# BANK34_35.net
KiCad netlist of a schematic drawn in Altium Designer
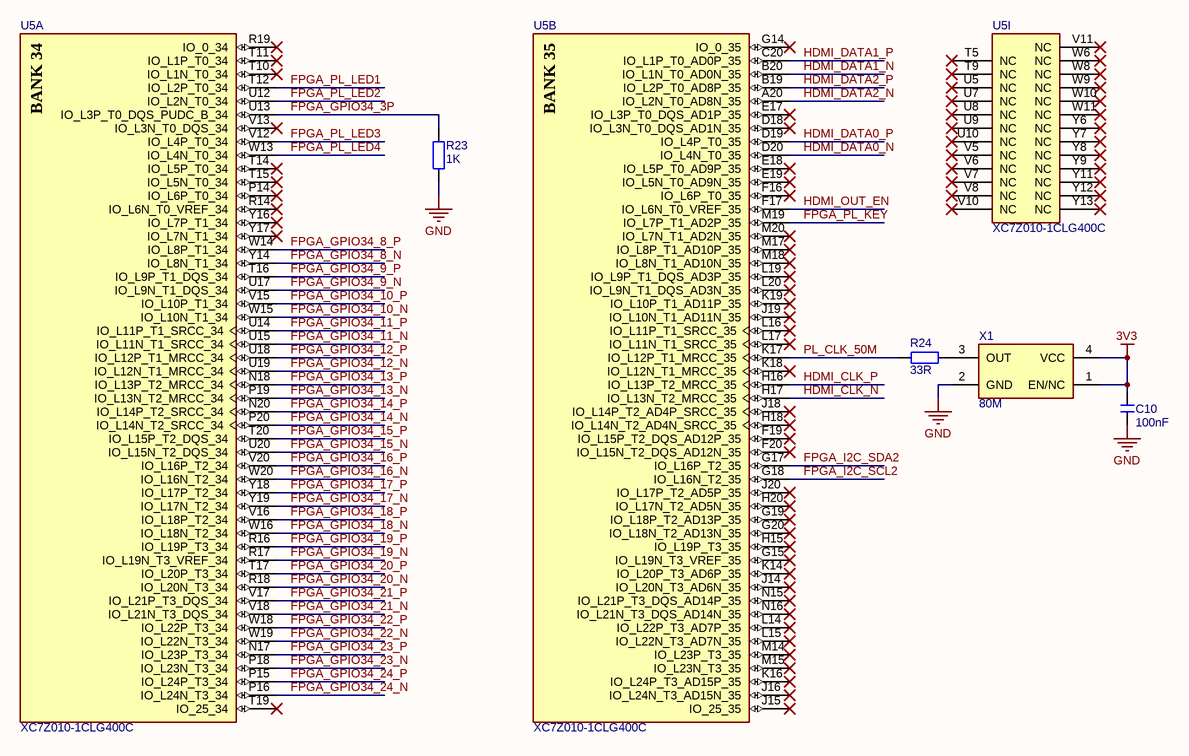
[diagram p0: BANK34_35.SchDoc]

(export (version "E")
  (design (tool "Eeschema 10.0.6"))
  (components
    (comp (ref "C10")
      (value "100nF")
      (footprint "C 0402_L")
      (description "无极性贴片电容")
      (fields (field (name "版权归属") "源创客"))
      (libsource (lib "3.1   - 电阻-电容-电感") (part "C"))
    )
    (comp (ref "R23")
      (value "1K")
      (footprint "R 0402_L")
      (description "贴片电阻")
      (fields (field (name "版权归属") "源创客"))
      (libsource (lib "3.1   - 电阻-电容-电感") (part "R"))
    )
    (comp (ref "R24")
      (value "33R")
      (footprint "R 0805_L")
      (description "贴片电阻")
      (fields (field (name "版权归属") "源创客"))
      (libsource (lib "3.1   - 电阻-电容-电感") (part "R"))
    )
    (comp (ref "U5")
      (value "XC7Z010-1CLG400C")
      (footprint "CLG400")
      (description "ZYNQ7000芯片")
      (libsource (lib "16.2 - Xilinx芯片") (part "XC7Z010-1CLG400C"))
    )
    (comp (ref "X1")
      (value "80M")
      (footprint "OSC 1612-4P")
      (description "4脚有源晶振")
      (fields (field (name "版权归属") "源创客"))
      (libsource (lib "10.1 - 保险丝-晶振") (part "XTAL-ACT-4P"))
    )
  )
  (nets
    (net (code "1") (name "/FPGA_GPIO34_3P") (class "Default")
      (node (ref "R23") (pin "1") (pinfunction "1_1") (pintype "passive"))
      (node (ref "U5") (pin "U13") (pinfunction "IO_L3P_T0_DQS_PUDC_B_34_U13") (pintype "bidirectional"))
    )
    (net (code "2") (name "/FPGA_GPIO34_8_N") (class "Default")
      (node (ref "U5") (pin "Y14") (pinfunction "IO_L8N_T1_34_Y14") (pintype "bidirectional"))
    )
    (net (code "3") (name "/FPGA_GPIO34_8_P") (class "Default")
      (node (ref "U5") (pin "W14") (pinfunction "IO_L8P_T1_34_W14") (pintype "bidirectional"))
    )
    (net (code "4") (name "/FPGA_GPIO34_9_N") (class "Default")
      (node (ref "U5") (pin "U17") (pinfunction "IO_L9N_T1_DQS_34_U17") (pintype "bidirectional"))
    )
    (net (code "5") (name "/FPGA_GPIO34_9_P") (class "Default")
      (node (ref "U5") (pin "T16") (pinfunction "IO_L9P_T1_DQS_34_T16") (pintype "bidirectional"))
    )
    (net (code "6") (name "/FPGA_GPIO34_10_N") (class "Default")
      (node (ref "U5") (pin "W15") (pinfunction "IO_L10N_T1_34_W15") (pintype "bidirectional"))
    )
    (net (code "7") (name "/FPGA_GPIO34_10_P") (class "Default")
      (node (ref "U5") (pin "V15") (pinfunction "IO_L10P_T1_34_V15") (pintype "bidirectional"))
    )
    (net (code "8") (name "/FPGA_GPIO34_11_N") (class "Default")
      (node (ref "U5") (pin "U15") (pinfunction "IO_L11N_T1_SRCC_34_U15") (pintype "bidirectional"))
    )
    (net (code "9") (name "/FPGA_GPIO34_11_P") (class "Default")
      (node (ref "U5") (pin "U14") (pinfunction "IO_L11P_T1_SRCC_34_U14") (pintype "bidirectional"))
    )
    (net (code "10") (name "/FPGA_GPIO34_12_N") (class "Default")
      (node (ref "U5") (pin "U19") (pinfunction "IO_L12N_T1_MRCC_34_U19") (pintype "bidirectional"))
    )
    (net (code "11") (name "/FPGA_GPIO34_12_P") (class "Default")
      (node (ref "U5") (pin "U18") (pinfunction "IO_L12P_T1_MRCC_34_U18") (pintype "bidirectional"))
    )
    (net (code "12") (name "/FPGA_GPIO34_13_N") (class "Default")
      (node (ref "U5") (pin "P19") (pinfunction "IO_L13N_T2_MRCC_34_P19") (pintype "bidirectional"))
    )
    (net (code "13") (name "/FPGA_GPIO34_13_P") (class "Default")
      (node (ref "U5") (pin "N18") (pinfunction "IO_L13P_T2_MRCC_34_N18") (pintype "bidirectional"))
    )
    (net (code "14") (name "/FPGA_GPIO34_14_N") (class "Default")
      (node (ref "U5") (pin "P20") (pinfunction "IO_L14N_T2_SRCC_34_P20") (pintype "bidirectional"))
    )
    (net (code "15") (name "/FPGA_GPIO34_14_P") (class "Default")
      (node (ref "U5") (pin "N20") (pinfunction "IO_L14P_T2_SRCC_34_N20") (pintype "bidirectional"))
    )
    (net (code "16") (name "/FPGA_GPIO34_15_N") (class "Default")
      (node (ref "U5") (pin "U20") (pinfunction "IO_L15N_T2_DQS_34_U20") (pintype "bidirectional"))
    )
    (net (code "17") (name "/FPGA_GPIO34_15_P") (class "Default")
      (node (ref "U5") (pin "T20") (pinfunction "IO_L15P_T2_DQS_34_T20") (pintype "bidirectional"))
    )
    (net (code "18") (name "/FPGA_GPIO34_16_N") (class "Default")
      (node (ref "U5") (pin "W20") (pinfunction "IO_L16N_T2_34_W20") (pintype "bidirectional"))
    )
    (net (code "19") (name "/FPGA_GPIO34_16_P") (class "Default")
      (node (ref "U5") (pin "V20") (pinfunction "IO_L16P_T2_34_V20") (pintype "bidirectional"))
    )
    (net (code "20") (name "/FPGA_GPIO34_17_N") (class "Default")
      (node (ref "U5") (pin "Y19") (pinfunction "IO_L17N_T2_34_Y19") (pintype "bidirectional"))
    )
    (net (code "21") (name "/FPGA_GPIO34_17_P") (class "Default")
      (node (ref "U5") (pin "Y18") (pinfunction "IO_L17P_T2_34_Y18") (pintype "bidirectional"))
    )
    (net (code "22") (name "/FPGA_GPIO34_18_N") (class "Default")
      (node (ref "U5") (pin "W16") (pinfunction "IO_L18N_T2_34_W16") (pintype "bidirectional"))
    )
    (net (code "23") (name "/FPGA_GPIO34_18_P") (class "Default")
      (node (ref "U5") (pin "V16") (pinfunction "IO_L18P_T2_34_V16") (pintype "bidirectional"))
    )
    (net (code "24") (name "/FPGA_GPIO34_19_N") (class "Default")
      (node (ref "U5") (pin "R17") (pinfunction "IO_L19N_T3_VREF_34_R17") (pintype "bidirectional"))
    )
    (net (code "25") (name "/FPGA_GPIO34_19_P") (class "Default")
      (node (ref "U5") (pin "R16") (pinfunction "IO_L19P_T3_34_R16") (pintype "bidirectional"))
    )
    (net (code "26") (name "/FPGA_GPIO34_20_N") (class "Default")
      (node (ref "U5") (pin "R18") (pinfunction "IO_L20N_T3_34_R18") (pintype "bidirectional"))
    )
    (net (code "27") (name "/FPGA_GPIO34_20_P") (class "Default")
      (node (ref "U5") (pin "T17") (pinfunction "IO_L20P_T3_34_T17") (pintype "bidirectional"))
    )
    (net (code "28") (name "/FPGA_GPIO34_21_N") (class "Default")
      (node (ref "U5") (pin "V18") (pinfunction "IO_L21N_T3_DQS_34_V18") (pintype "bidirectional"))
    )
    (net (code "29") (name "/FPGA_GPIO34_21_P") (class "Default")
      (node (ref "U5") (pin "V17") (pinfunction "IO_L21P_T3_DQS_34_V17") (pintype "bidirectional"))
    )
    (net (code "30") (name "/FPGA_GPIO34_22_N") (class "Default")
      (node (ref "U5") (pin "W19") (pinfunction "IO_L22N_T3_34_W19") (pintype "bidirectional"))
    )
    (net (code "31") (name "/FPGA_GPIO34_22_P") (class "Default")
      (node (ref "U5") (pin "W18") (pinfunction "IO_L22P_T3_34_W18") (pintype "bidirectional"))
    )
    (net (code "32") (name "/FPGA_GPIO34_23_N") (class "Default")
      (node (ref "U5") (pin "P18") (pinfunction "IO_L23N_T3_34_P18") (pintype "bidirectional"))
    )
    (net (code "33") (name "/FPGA_GPIO34_23_P") (class "Default")
      (node (ref "U5") (pin "N17") (pinfunction "IO_L23P_T3_34_N17") (pintype "bidirectional"))
    )
    (net (code "34") (name "/FPGA_GPIO34_24_N") (class "Default")
      (node (ref "U5") (pin "P16") (pinfunction "IO_L24N_T3_34_P16") (pintype "bidirectional"))
    )
    (net (code "35") (name "/FPGA_GPIO34_24_P") (class "Default")
      (node (ref "U5") (pin "P15") (pinfunction "IO_L24P_T3_34_P15") (pintype "bidirectional"))
    )
    (net (code "36") (name "/FPGA_I2C_SCL2") (class "Default")
      (node (ref "U5") (pin "G18") (pinfunction "IO_L16N_T2_35_G18") (pintype "bidirectional"))
    )
    (net (code "37") (name "/FPGA_I2C_SDA2") (class "Default")
      (node (ref "U5") (pin "G17") (pinfunction "IO_L16P_T2_35_G17") (pintype "bidirectional"))
    )
    (net (code "38") (name "/FPGA_PL_KEY") (class "Default")
      (node (ref "U5") (pin "M19") (pinfunction "IO_L7P_T1_AD2P_35_M19") (pintype "bidirectional"))
    )
    (net (code "39") (name "/FPGA_PL_LED1") (class "Default")
      (node (ref "U5") (pin "T12") (pinfunction "IO_L2P_T0_34_T12") (pintype "bidirectional"))
    )
    (net (code "40") (name "/FPGA_PL_LED2") (class "Default")
      (node (ref "U5") (pin "U12") (pinfunction "IO_L2N_T0_34_U12") (pintype "bidirectional"))
    )
    (net (code "41") (name "/FPGA_PL_LED3") (class "Default")
      (node (ref "U5") (pin "V12") (pinfunction "IO_L4P_T0_34_V12") (pintype "bidirectional"))
    )
    (net (code "42") (name "/FPGA_PL_LED4") (class "Default")
      (node (ref "U5") (pin "W13") (pinfunction "IO_L4N_T0_34_W13") (pintype "bidirectional"))
    )
    (net (code "43") (name "/HDMI_CLK_N") (class "Default")
      (node (ref "U5") (pin "H17") (pinfunction "IO_L13N_T2_MRCC_35_H17") (pintype "bidirectional"))
    )
    (net (code "44") (name "/HDMI_CLK_P") (class "Default")
      (node (ref "U5") (pin "H16") (pinfunction "IO_L13P_T2_MRCC_35_H16") (pintype "bidirectional"))
    )
    (net (code "45") (name "/HDMI_DATA0_N") (class "Default")
      (node (ref "U5") (pin "D20") (pinfunction "IO_L4N_T0_35_D20") (pintype "bidirectional"))
    )
    (net (code "46") (name "/HDMI_DATA0_P") (class "Default")
      (node (ref "U5") (pin "D19") (pinfunction "IO_L4P_T0_35_D19") (pintype "bidirectional"))
    )
    (net (code "47") (name "/HDMI_DATA1_N") (class "Default")
      (node (ref "U5") (pin "B20") (pinfunction "IO_L1N_T0_AD0N_35_B20") (pintype "bidirectional"))
    )
    (net (code "48") (name "/HDMI_DATA1_P") (class "Default")
      (node (ref "U5") (pin "C20") (pinfunction "IO_L1P_T0_AD0P_35_C20") (pintype "bidirectional"))
    )
    (net (code "49") (name "/HDMI_DATA2_N") (class "Default")
      (node (ref "U5") (pin "A20") (pinfunction "IO_L2N_T0_AD8N_35_A20") (pintype "bidirectional"))
    )
    (net (code "50") (name "/HDMI_DATA2_P") (class "Default")
      (node (ref "U5") (pin "B19") (pinfunction "IO_L2P_T0_AD8P_35_B19") (pintype "bidirectional"))
    )
    (net (code "51") (name "/HDMI_OUT_EN") (class "Default")
      (node (ref "U5") (pin "F17") (pinfunction "IO_L6N_T0_VREF_35_F17") (pintype "bidirectional"))
    )
    (net (code "52") (name "/PL_CLK_50M") (class "Default")
      (node (ref "R24") (pin "2") (pinfunction "2_2") (pintype "passive"))
      (node (ref "U5") (pin "K17") (pinfunction "IO_L12P_T1_MRCC_35_K17") (pintype "bidirectional"))
    )
    (net (code "53") (name "3V3") (class "Default")
      (node (ref "C10") (pin "2") (pinfunction "2_2") (pintype "passive"))
      (node (ref "X1") (pin "1") (pinfunction "EN/NC_1") (pintype "passive"))
      (node (ref "X1") (pin "4") (pinfunction "VCC_4") (pintype "passive"))
    )
    (net (code "54") (name "GND") (class "Default")
      (node (ref "C10") (pin "1") (pinfunction "1_1") (pintype "passive"))
      (node (ref "R23") (pin "2") (pinfunction "2_2") (pintype "passive"))
      (node (ref "X1") (pin "2") (pinfunction "GND_2") (pintype "passive"))
    )
    (net (code "55") (name "Net-(X1-OUT)") (class "Default")
      (node (ref "R24") (pin "1") (pinfunction "1_1") (pintype "passive"))
      (node (ref "X1") (pin "3") (pinfunction "OUT_3") (pintype "passive"))
    )
    (net (code "56") (name "unconnected-(U5A-IO_0_34-PadR19)") (class "Default")
      (node (ref "U5") (pin "R19") (pinfunction "IO_0_34_R19") (pintype "bidirectional+no_connect"))
    )
    (net (code "57") (name "unconnected-(U5A-IO_25_34-PadT19)") (class "Default")
      (node (ref "U5") (pin "T19") (pinfunction "IO_25_34_T19") (pintype "bidirectional+no_connect"))
    )
    (net (code "58") (name "unconnected-(U5A-IO_L1N_T0_34-PadT10)") (class "Default")
      (node (ref "U5") (pin "T10") (pinfunction "IO_L1N_T0_34_T10") (pintype "bidirectional+no_connect"))
    )
    (net (code "59") (name "unconnected-(U5A-IO_L1P_T0_34-PadT11)") (class "Default")
      (node (ref "U5") (pin "T11") (pinfunction "IO_L1P_T0_34_T11") (pintype "bidirectional+no_connect"))
    )
    (net (code "60") (name "unconnected-(U5A-IO_L3N_T0_DQS_34-PadV13)") (class "Default")
      (node (ref "U5") (pin "V13") (pinfunction "IO_L3N_T0_DQS_34_V13") (pintype "bidirectional+no_connect"))
    )
    (net (code "61") (name "unconnected-(U5A-IO_L5N_T0_34-PadT15)") (class "Default")
      (node (ref "U5") (pin "T15") (pinfunction "IO_L5N_T0_34_T15") (pintype "bidirectional+no_connect"))
    )
    (net (code "62") (name "unconnected-(U5A-IO_L5P_T0_34-PadT14)") (class "Default")
      (node (ref "U5") (pin "T14") (pinfunction "IO_L5P_T0_34_T14") (pintype "bidirectional+no_connect"))
    )
    (net (code "63") (name "unconnected-(U5A-IO_L6N_T0_VREF_34-PadR14)") (class "Default")
      (node (ref "U5") (pin "R14") (pinfunction "IO_L6N_T0_VREF_34_R14") (pintype "bidirectional+no_connect"))
    )
    (net (code "64") (name "unconnected-(U5A-IO_L6P_T0_34-PadP14)") (class "Default")
      (node (ref "U5") (pin "P14") (pinfunction "IO_L6P_T0_34_P14") (pintype "bidirectional+no_connect"))
    )
    (net (code "65") (name "unconnected-(U5A-IO_L7N_T1_34-PadY17)") (class "Default")
      (node (ref "U5") (pin "Y17") (pinfunction "IO_L7N_T1_34_Y17") (pintype "bidirectional+no_connect"))
    )
    (net (code "66") (name "unconnected-(U5A-IO_L7P_T1_34-PadY16)") (class "Default")
      (node (ref "U5") (pin "Y16") (pinfunction "IO_L7P_T1_34_Y16") (pintype "bidirectional+no_connect"))
    )
    (net (code "67") (name "unconnected-(U5B-IO_0_35-PadG14)") (class "Default")
      (node (ref "U5") (pin "G14") (pinfunction "IO_0_35_G14") (pintype "bidirectional+no_connect"))
    )
    (net (code "68") (name "unconnected-(U5B-IO_25_35-PadJ15)") (class "Default")
      (node (ref "U5") (pin "J15") (pinfunction "IO_25_35_J15") (pintype "bidirectional+no_connect"))
    )
    (net (code "69") (name "unconnected-(U5B-IO_L3N_T0_DQS_AD1N_35-PadD18)") (class "Default")
      (node (ref "U5") (pin "D18") (pinfunction "IO_L3N_T0_DQS_AD1N_35_D18") (pintype "bidirectional+no_connect"))
    )
    (net (code "70") (name "unconnected-(U5B-IO_L3P_T0_DQS_AD1P_35-PadE17)") (class "Default")
      (node (ref "U5") (pin "E17") (pinfunction "IO_L3P_T0_DQS_AD1P_35_E17") (pintype "bidirectional+no_connect"))
    )
    (net (code "71") (name "unconnected-(U5B-IO_L5N_T0_AD9N_35-PadE19)") (class "Default")
      (node (ref "U5") (pin "E19") (pinfunction "IO_L5N_T0_AD9N_35_E19") (pintype "bidirectional+no_connect"))
    )
    (net (code "72") (name "unconnected-(U5B-IO_L5P_T0_AD9P_35-PadE18)") (class "Default")
      (node (ref "U5") (pin "E18") (pinfunction "IO_L5P_T0_AD9P_35_E18") (pintype "bidirectional+no_connect"))
    )
    (net (code "73") (name "unconnected-(U5B-IO_L6P_T0_35-PadF16)") (class "Default")
      (node (ref "U5") (pin "F16") (pinfunction "IO_L6P_T0_35_F16") (pintype "bidirectional+no_connect"))
    )
    (net (code "74") (name "unconnected-(U5B-IO_L7N_T1_AD2N_35-PadM20)") (class "Default")
      (node (ref "U5") (pin "M20") (pinfunction "IO_L7N_T1_AD2N_35_M20") (pintype "bidirectional+no_connect"))
    )
    (net (code "75") (name "unconnected-(U5B-IO_L8N_T1_AD10N_35-PadM18)") (class "Default")
      (node (ref "U5") (pin "M18") (pinfunction "IO_L8N_T1_AD10N_35_M18") (pintype "bidirectional+no_connect"))
    )
    (net (code "76") (name "unconnected-(U5B-IO_L8P_T1_AD10P_35-PadM17)") (class "Default")
      (node (ref "U5") (pin "M17") (pinfunction "IO_L8P_T1_AD10P_35_M17") (pintype "bidirectional+no_connect"))
    )
    (net (code "77") (name "unconnected-(U5B-IO_L9N_T1_DQS_AD3N_35-PadL20)") (class "Default")
      (node (ref "U5") (pin "L20") (pinfunction "IO_L9N_T1_DQS_AD3N_35_L20") (pintype "bidirectional+no_connect"))
    )
    (net (code "78") (name "unconnected-(U5B-IO_L9P_T1_DQS_AD3P_35-PadL19)") (class "Default")
      (node (ref "U5") (pin "L19") (pinfunction "IO_L9P_T1_DQS_AD3P_35_L19") (pintype "bidirectional+no_connect"))
    )
    (net (code "79") (name "unconnected-(U5B-IO_L10N_T1_AD11N_35-PadJ19)") (class "Default")
      (node (ref "U5") (pin "J19") (pinfunction "IO_L10N_T1_AD11N_35_J19") (pintype "bidirectional+no_connect"))
    )
    (net (code "80") (name "unconnected-(U5B-IO_L10P_T1_AD11P_35-PadK19)") (class "Default")
      (node (ref "U5") (pin "K19") (pinfunction "IO_L10P_T1_AD11P_35_K19") (pintype "bidirectional+no_connect"))
    )
    (net (code "81") (name "unconnected-(U5B-IO_L11N_T1_SRCC_35-PadL17)") (class "Default")
      (node (ref "U5") (pin "L17") (pinfunction "IO_L11N_T1_SRCC_35_L17") (pintype "bidirectional+no_connect"))
    )
    (net (code "82") (name "unconnected-(U5B-IO_L11P_T1_SRCC_35-PadL16)") (class "Default")
      (node (ref "U5") (pin "L16") (pinfunction "IO_L11P_T1_SRCC_35_L16") (pintype "bidirectional+no_connect"))
    )
    (net (code "83") (name "unconnected-(U5B-IO_L12N_T1_MRCC_35-PadK18)") (class "Default")
      (node (ref "U5") (pin "K18") (pinfunction "IO_L12N_T1_MRCC_35_K18") (pintype "bidirectional+no_connect"))
    )
    (net (code "84") (name "unconnected-(U5B-IO_L14N_T2_AD4N_SRCC_35-PadH18)") (class "Default")
      (node (ref "U5") (pin "H18") (pinfunction "IO_L14N_T2_AD4N_SRCC_35_H18") (pintype "bidirectional+no_connect"))
    )
    (net (code "85") (name "unconnected-(U5B-IO_L14P_T2_AD4P_SRCC_35-PadJ18)") (class "Default")
      (node (ref "U5") (pin "J18") (pinfunction "IO_L14P_T2_AD4P_SRCC_35_J18") (pintype "bidirectional+no_connect"))
    )
    (net (code "86") (name "unconnected-(U5B-IO_L15N_T2_DQS_AD12N_35-PadF20)") (class "Default")
      (node (ref "U5") (pin "F20") (pinfunction "IO_L15N_T2_DQS_AD12N_35_F20") (pintype "bidirectional+no_connect"))
    )
    (net (code "87") (name "unconnected-(U5B-IO_L15P_T2_DQS_AD12P_35-PadF19)") (class "Default")
      (node (ref "U5") (pin "F19") (pinfunction "IO_L15P_T2_DQS_AD12P_35_F19") (pintype "bidirectional+no_connect"))
    )
    (net (code "88") (name "unconnected-(U5B-IO_L17N_T2_AD5N_35-PadH20)") (class "Default")
      (node (ref "U5") (pin "H20") (pinfunction "IO_L17N_T2_AD5N_35_H20") (pintype "bidirectional+no_connect"))
    )
    (net (code "89") (name "unconnected-(U5B-IO_L17P_T2_AD5P_35-PadJ20)") (class "Default")
      (node (ref "U5") (pin "J20") (pinfunction "IO_L17P_T2_AD5P_35_J20") (pintype "bidirectional+no_connect"))
    )
    (net (code "90") (name "unconnected-(U5B-IO_L18N_T2_AD13N_35-PadG20)") (class "Default")
      (node (ref "U5") (pin "G20") (pinfunction "IO_L18N_T2_AD13N_35_G20") (pintype "bidirectional+no_connect"))
    )
    (net (code "91") (name "unconnected-(U5B-IO_L18P_T2_AD13P_35-PadG19)") (class "Default")
      (node (ref "U5") (pin "G19") (pinfunction "IO_L18P_T2_AD13P_35_G19") (pintype "bidirectional+no_connect"))
    )
    (net (code "92") (name "unconnected-(U5B-IO_L19N_T3_VREF_35-PadG15)") (class "Default")
      (node (ref "U5") (pin "G15") (pinfunction "IO_L19N_T3_VREF_35_G15") (pintype "bidirectional+no_connect"))
    )
    (net (code "93") (name "unconnected-(U5B-IO_L19P_T3_35-PadH15)") (class "Default")
      (node (ref "U5") (pin "H15") (pinfunction "IO_L19P_T3_35_H15") (pintype "bidirectional+no_connect"))
    )
    (net (code "94") (name "unconnected-(U5B-IO_L20N_T3_AD6N_35-PadJ14)") (class "Default")
      (node (ref "U5") (pin "J14") (pinfunction "IO_L20N_T3_AD6N_35_J14") (pintype "bidirectional+no_connect"))
    )
    (net (code "95") (name "unconnected-(U5B-IO_L20P_T3_AD6P_35-PadK14)") (class "Default")
      (node (ref "U5") (pin "K14") (pinfunction "IO_L20P_T3_AD6P_35_K14") (pintype "bidirectional+no_connect"))
    )
    (net (code "96") (name "unconnected-(U5B-IO_L21N_T3_DQS_AD14N_35-PadN16)") (class "Default")
      (node (ref "U5") (pin "N16") (pinfunction "IO_L21N_T3_DQS_AD14N_35_N16") (pintype "bidirectional+no_connect"))
    )
    (net (code "97") (name "unconnected-(U5B-IO_L21P_T3_DQS_AD14P_35-PadN15)") (class "Default")
      (node (ref "U5") (pin "N15") (pinfunction "IO_L21P_T3_DQS_AD14P_35_N15") (pintype "bidirectional+no_connect"))
    )
    (net (code "98") (name "unconnected-(U5B-IO_L22N_T3_AD7N_35-PadL15)") (class "Default")
      (node (ref "U5") (pin "L15") (pinfunction "IO_L22N_T3_AD7N_35_L15") (pintype "bidirectional+no_connect"))
    )
    (net (code "99") (name "unconnected-(U5B-IO_L22P_T3_AD7P_35-PadL14)") (class "Default")
      (node (ref "U5") (pin "L14") (pinfunction "IO_L22P_T3_AD7P_35_L14") (pintype "bidirectional+no_connect"))
    )
    (net (code "100") (name "unconnected-(U5B-IO_L23N_T3_35-PadM15)") (class "Default")
      (node (ref "U5") (pin "M15") (pinfunction "IO_L23N_T3_35_M15") (pintype "bidirectional+no_connect"))
    )
    (net (code "101") (name "unconnected-(U5B-IO_L23P_T3_35-PadM14)") (class "Default")
      (node (ref "U5") (pin "M14") (pinfunction "IO_L23P_T3_35_M14") (pintype "bidirectional+no_connect"))
    )
    (net (code "102") (name "unconnected-(U5B-IO_L24N_T3_AD15N_35-PadJ16)") (class "Default")
      (node (ref "U5") (pin "J16") (pinfunction "IO_L24N_T3_AD15N_35_J16") (pintype "bidirectional+no_connect"))
    )
    (net (code "103") (name "unconnected-(U5B-IO_L24P_T3_AD15P_35-PadK16)") (class "Default")
      (node (ref "U5") (pin "K16") (pinfunction "IO_L24P_T3_AD15P_35_K16") (pintype "bidirectional+no_connect"))
    )
    (net (code "104") (name "unconnected-(U5I-NC-PadT5)") (class "Default")
      (node (ref "U5") (pin "T5") (pinfunction "NC_T5") (pintype "passive+no_connect"))
    )
    (net (code "105") (name "unconnected-(U5I-NC-PadT9)") (class "Default")
      (node (ref "U5") (pin "T9") (pinfunction "NC_T9") (pintype "passive+no_connect"))
    )
    (net (code "106") (name "unconnected-(U5I-NC-PadU5)") (class "Default")
      (node (ref "U5") (pin "U5") (pinfunction "NC_U5") (pintype "passive+no_connect"))
    )
    (net (code "107") (name "unconnected-(U5I-NC-PadU7)") (class "Default")
      (node (ref "U5") (pin "U7") (pinfunction "NC_U7") (pintype "passive+no_connect"))
    )
    (net (code "108") (name "unconnected-(U5I-NC-PadU8)") (class "Default")
      (node (ref "U5") (pin "U8") (pinfunction "NC_U8") (pintype "passive+no_connect"))
    )
    (net (code "109") (name "unconnected-(U5I-NC-PadU9)") (class "Default")
      (node (ref "U5") (pin "U9") (pinfunction "NC_U9") (pintype "passive+no_connect"))
    )
    (net (code "110") (name "unconnected-(U5I-NC-PadU10)") (class "Default")
      (node (ref "U5") (pin "U10") (pinfunction "NC_U10") (pintype "passive+no_connect"))
    )
    (net (code "111") (name "unconnected-(U5I-NC-PadV5)") (class "Default")
      (node (ref "U5") (pin "V5") (pinfunction "NC_V5") (pintype "passive+no_connect"))
    )
    (net (code "112") (name "unconnected-(U5I-NC-PadV6)") (class "Default")
      (node (ref "U5") (pin "V6") (pinfunction "NC_V6") (pintype "passive+no_connect"))
    )
    (net (code "113") (name "unconnected-(U5I-NC-PadV7)") (class "Default")
      (node (ref "U5") (pin "V7") (pinfunction "NC_V7") (pintype "passive+no_connect"))
    )
    (net (code "114") (name "unconnected-(U5I-NC-PadV8)") (class "Default")
      (node (ref "U5") (pin "V8") (pinfunction "NC_V8") (pintype "passive+no_connect"))
    )
    (net (code "115") (name "unconnected-(U5I-NC-PadV10)") (class "Default")
      (node (ref "U5") (pin "V10") (pinfunction "NC_V10") (pintype "passive+no_connect"))
    )
    (net (code "116") (name "unconnected-(U5I-NC-PadV11)") (class "Default")
      (node (ref "U5") (pin "V11") (pinfunction "NC_V11") (pintype "passive+no_connect"))
    )
    (net (code "117") (name "unconnected-(U5I-NC-PadW6)") (class "Default")
      (node (ref "U5") (pin "W6") (pinfunction "NC_W6") (pintype "passive+no_connect"))
    )
    (net (code "118") (name "unconnected-(U5I-NC-PadW8)") (class "Default")
      (node (ref "U5") (pin "W8") (pinfunction "NC_W8") (pintype "passive+no_connect"))
    )
    (net (code "119") (name "unconnected-(U5I-NC-PadW9)") (class "Default")
      (node (ref "U5") (pin "W9") (pinfunction "NC_W9") (pintype "passive+no_connect"))
    )
    (net (code "120") (name "unconnected-(U5I-NC-PadW10)") (class "Default")
      (node (ref "U5") (pin "W10") (pinfunction "NC_W10") (pintype "passive+no_connect"))
    )
    (net (code "121") (name "unconnected-(U5I-NC-PadW11)") (class "Default")
      (node (ref "U5") (pin "W11") (pinfunction "NC_W11") (pintype "passive+no_connect"))
    )
    (net (code "122") (name "unconnected-(U5I-NC-PadY6)") (class "Default")
      (node (ref "U5") (pin "Y6") (pinfunction "NC_Y6") (pintype "passive+no_connect"))
    )
    (net (code "123") (name "unconnected-(U5I-NC-PadY7)") (class "Default")
      (node (ref "U5") (pin "Y7") (pinfunction "NC_Y7") (pintype "passive+no_connect"))
    )
    (net (code "124") (name "unconnected-(U5I-NC-PadY8)") (class "Default")
      (node (ref "U5") (pin "Y8") (pinfunction "NC_Y8") (pintype "passive+no_connect"))
    )
    (net (code "125") (name "unconnected-(U5I-NC-PadY9)") (class "Default")
      (node (ref "U5") (pin "Y9") (pinfunction "NC_Y9") (pintype "passive+no_connect"))
    )
    (net (code "126") (name "unconnected-(U5I-NC-PadY11)") (class "Default")
      (node (ref "U5") (pin "Y11") (pinfunction "NC_Y11") (pintype "passive+no_connect"))
    )
    (net (code "127") (name "unconnected-(U5I-NC-PadY12)") (class "Default")
      (node (ref "U5") (pin "Y12") (pinfunction "NC_Y12") (pintype "passive+no_connect"))
    )
    (net (code "128") (name "unconnected-(U5I-NC-PadY13)") (class "Default")
      (node (ref "U5") (pin "Y13") (pinfunction "NC_Y13") (pintype "passive+no_connect"))
    )
  )
)
